# DRIVER.net
KiCad netlist of a schematic drawn in Altium Designer
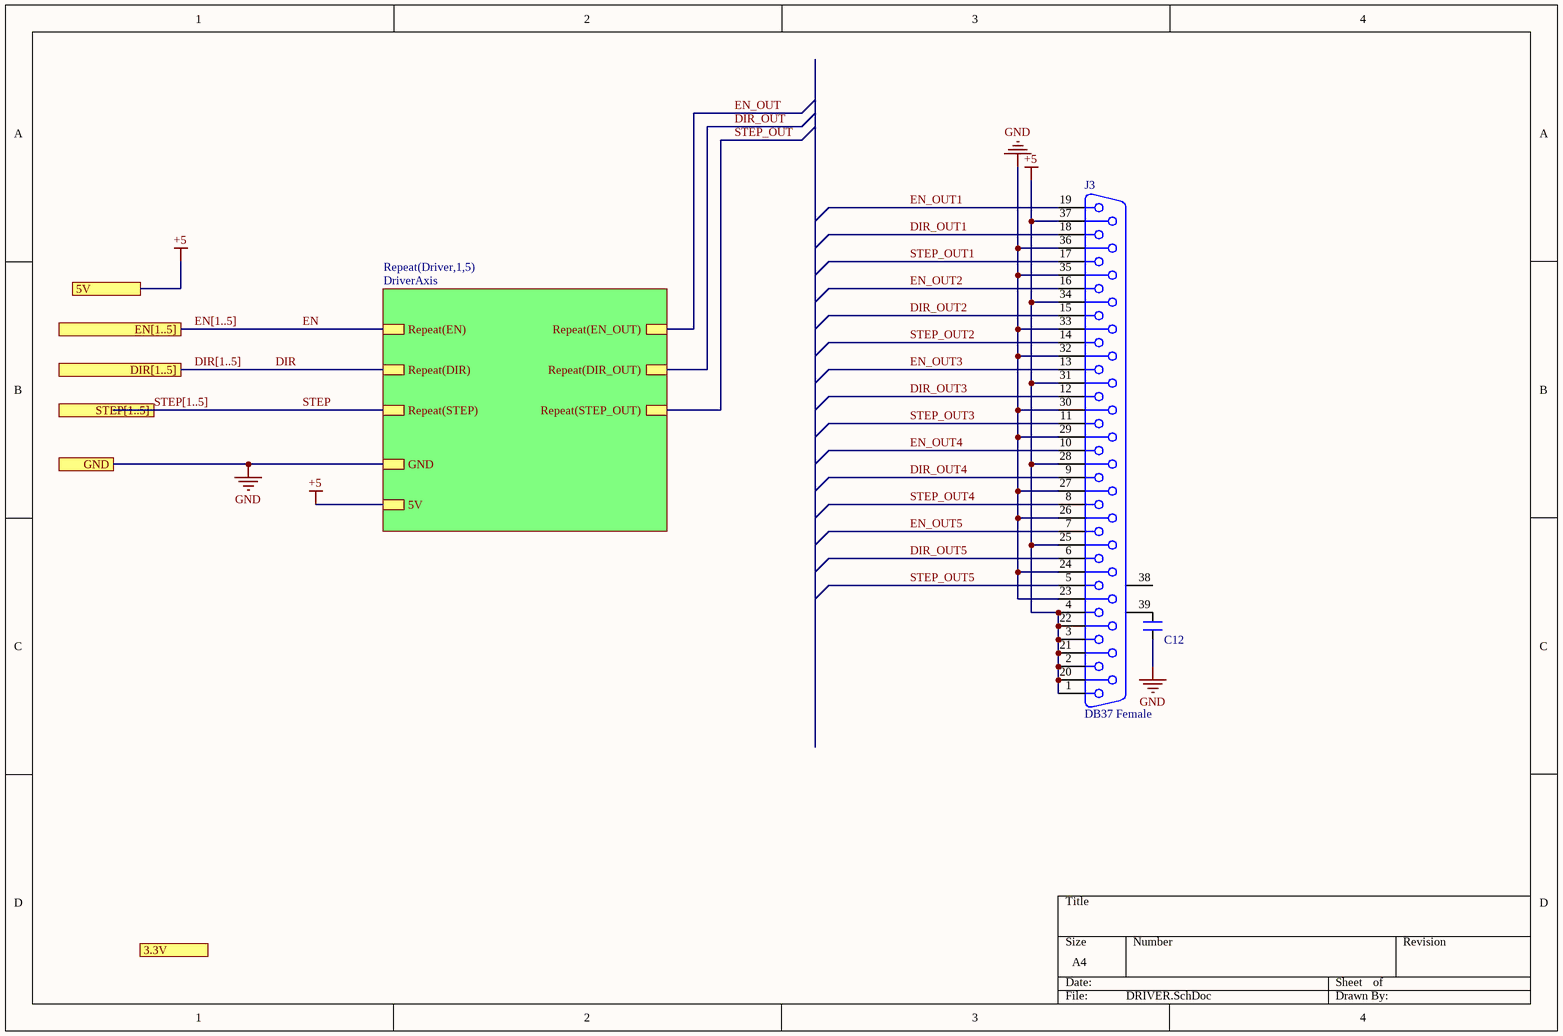
[diagram p0: DRIVER.SchDoc]

(export (version "E")
  (design (tool "Eeschema 10.0.6"))
  (components
    (comp (ref "C12") (value "10uF") (footprint "CN-SMD-0603_big") (libsource (lib "nhan") (part "CN")))
    (comp (ref "J3") (value "DB37 Female") (footprint "DB37") (libsource (lib "nhan") (part "DB37 Female")))
  )
  (nets
    (net (code "16") (name "+5") (class "Default")
      (node (ref "J3") (pin "1") (pinfunction "1_1") (pintype "passive"))
      (node (ref "J3") (pin "2") (pinfunction "2_2") (pintype "passive"))
      (node (ref "J3") (pin "20") (pinfunction "20_20") (pintype "passive"))
      (node (ref "J3") (pin "21") (pinfunction "21_21") (pintype "passive"))
      (node (ref "J3") (pin "22") (pinfunction "22_22") (pintype "passive"))
      (node (ref "J3") (pin "25") (pinfunction "25_25") (pintype "passive"))
      (node (ref "J3") (pin "28") (pinfunction "28_28") (pintype "passive"))
      (node (ref "J3") (pin "3") (pinfunction "3_3") (pintype "passive"))
      (node (ref "J3") (pin "31") (pinfunction "31_31") (pintype "passive"))
      (node (ref "J3") (pin "34") (pinfunction "34_34") (pintype "passive"))
      (node (ref "J3") (pin "37") (pinfunction "37_37") (pintype "passive"))
      (node (ref "J3") (pin "4") (pinfunction "4_4") (pintype "passive"))
    )
    (net (code "21") (name "/DIR_OUT1") (class "Default")
      (node (ref "J3") (pin "18") (pinfunction "18_18") (pintype "passive"))
    )
    (net (code "22") (name "/DIR_OUT2") (class "Default")
      (node (ref "J3") (pin "15") (pinfunction "15_15") (pintype "passive"))
    )
    (net (code "23") (name "/DIR_OUT3") (class "Default")
      (node (ref "J3") (pin "12") (pinfunction "12_12") (pintype "passive"))
    )
    (net (code "24") (name "/DIR_OUT4") (class "Default")
      (node (ref "J3") (pin "9") (pinfunction "9_9") (pintype "passive"))
    )
    (net (code "25") (name "/DIR_OUT5") (class "Default")
      (node (ref "J3") (pin "6") (pinfunction "6_6") (pintype "passive"))
    )
    (net (code "29") (name "/EN_OUT1") (class "Default")
      (node (ref "J3") (pin "19") (pinfunction "19_19") (pintype "passive"))
    )
    (net (code "30") (name "/EN_OUT2") (class "Default")
      (node (ref "J3") (pin "16") (pinfunction "16_16") (pintype "passive"))
    )
    (net (code "31") (name "/EN_OUT3") (class "Default")
      (node (ref "J3") (pin "13") (pinfunction "13_13") (pintype "passive"))
    )
    (net (code "32") (name "/EN_OUT4") (class "Default")
      (node (ref "J3") (pin "10") (pinfunction "10_10") (pintype "passive"))
    )
    (net (code "33") (name "/EN_OUT5") (class "Default")
      (node (ref "J3") (pin "7") (pinfunction "7_7") (pintype "passive"))
    )
    (net (code "37") (name "/STEP_OUT1") (class "Default")
      (node (ref "J3") (pin "17") (pinfunction "17_17") (pintype "passive"))
    )
    (net (code "38") (name "/STEP_OUT2") (class "Default")
      (node (ref "J3") (pin "14") (pinfunction "14_14") (pintype "passive"))
    )
    (net (code "39") (name "/STEP_OUT3") (class "Default")
      (node (ref "J3") (pin "11") (pinfunction "11_11") (pintype "passive"))
    )
    (net (code "40") (name "/STEP_OUT4") (class "Default")
      (node (ref "J3") (pin "8") (pinfunction "8_8") (pintype "passive"))
    )
    (net (code "41") (name "/STEP_OUT5") (class "Default")
      (node (ref "J3") (pin "5") (pinfunction "5_5") (pintype "passive"))
    )
    (net (code "42") (name "GND") (class "Default")
      (node (ref "C12") (pin "1") (pinfunction "1_1") (pintype "passive"))
      (node (ref "J3") (pin "23") (pinfunction "23_23") (pintype "passive"))
      (node (ref "J3") (pin "24") (pinfunction "24_24") (pintype "passive"))
      (node (ref "J3") (pin "26") (pinfunction "26_26") (pintype "passive"))
      (node (ref "J3") (pin "27") (pinfunction "27_27") (pintype "passive"))
      (node (ref "J3") (pin "29") (pinfunction "29_29") (pintype "passive"))
      (node (ref "J3") (pin "30") (pinfunction "30_30") (pintype "passive"))
      (node (ref "J3") (pin "32") (pinfunction "32_32") (pintype "passive"))
      (node (ref "J3") (pin "33") (pinfunction "33_33") (pintype "passive"))
      (node (ref "J3") (pin "35") (pinfunction "35_35") (pintype "passive"))
      (node (ref "J3") (pin "36") (pinfunction "36_36") (pintype "passive"))
    )
    (net (code "43") (name "Net-(J3-MH2)") (class "Default")
      (node (ref "C12") (pin "2") (pinfunction "2_2") (pintype "passive"))
      (node (ref "J3") (pin "39") (pinfunction "MH2_39") (pintype "passive"))
    )
    (net (code "44") (name "unconnected-(J3-MH1-Pad38)") (class "Default")
      (node (ref "J3") (pin "38") (pinfunction "MH1_38") (pintype "passive"))
    )
  )
)
